# charger.net
KiCad netlist of a schematic drawn in Altium Designer
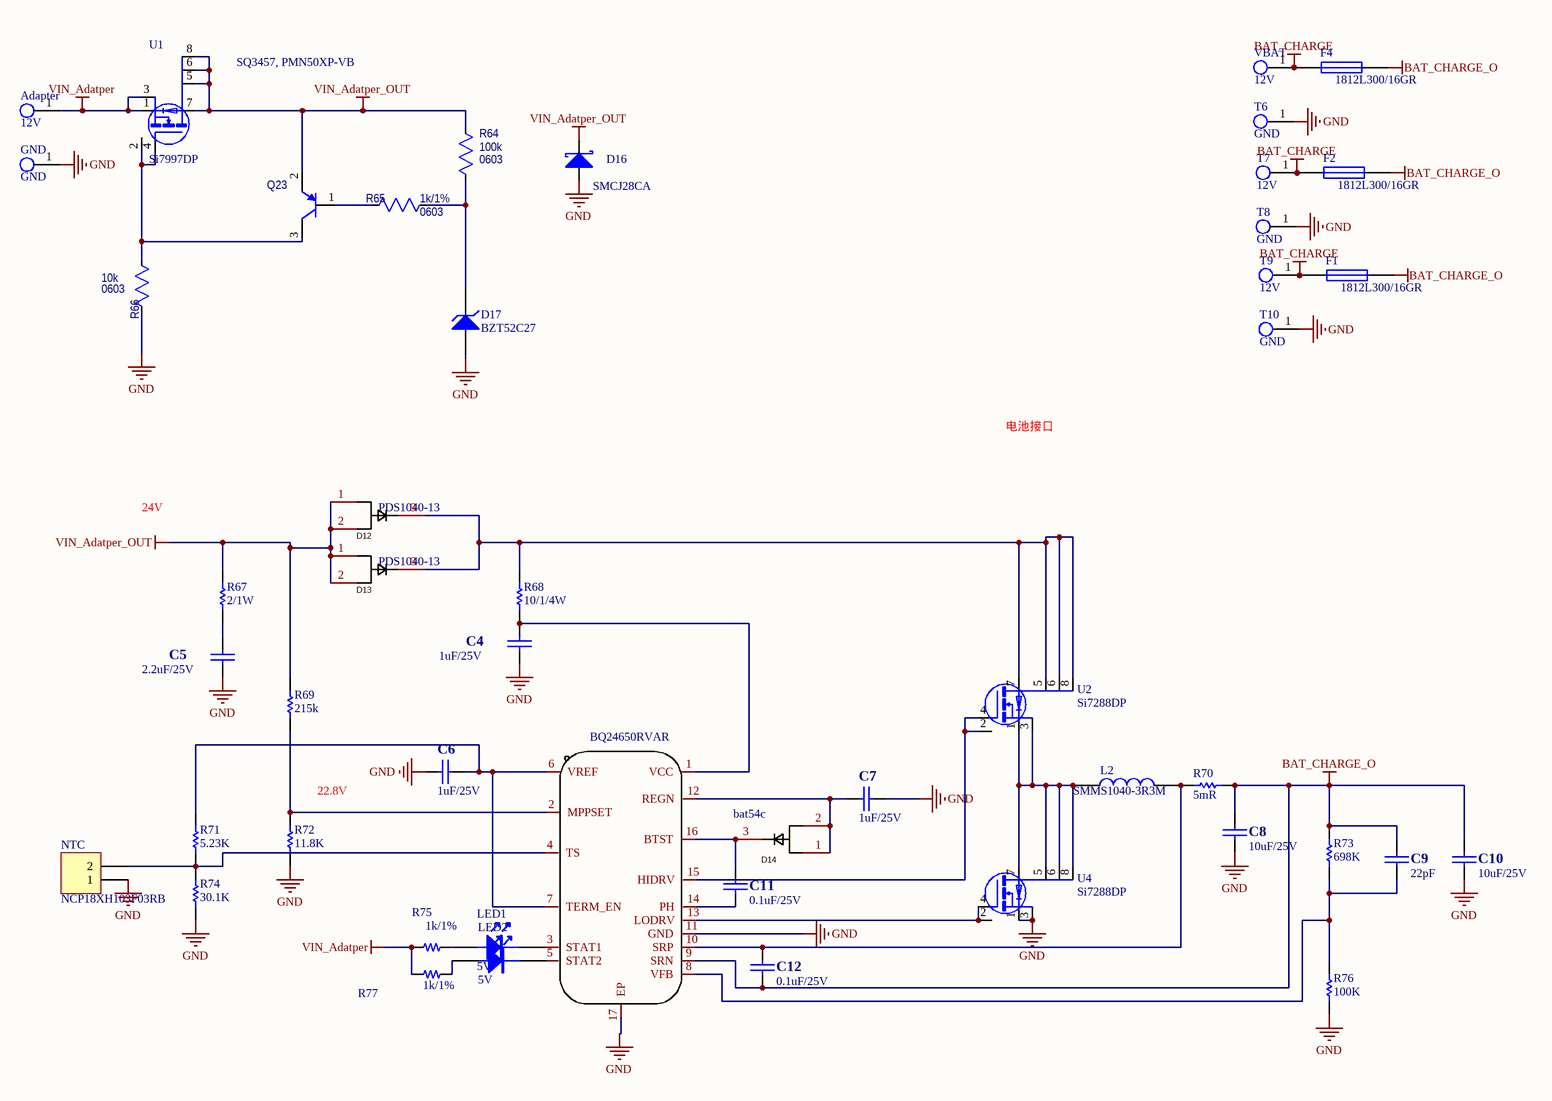
[diagram p0: charger.SchDoc]

(export (version "E")
  (design (tool "Eeschema 10.0.6"))
  (components
    (comp (ref "Adapter") (value "12V") (footprint "FIX-4.5") (libsource (lib "Schlib_20110825") (part "TP")))
    (comp (ref "C4")
      (value "1uF/25V")
      (footprint "0805C")
      (description "Capacitor")
      (libsource (lib "*") (part "CAP"))
    )
    (comp (ref "C5")
      (value "2.2uF/25V")
      (footprint "1210C")
      (description "Capacitor")
      (libsource (lib "*") (part "CAP"))
    )
    (comp (ref "C6")
      (value "1uF/25V")
      (footprint "0603C")
      (description "Capacitor")
      (libsource (lib "*") (part "CAP"))
    )
    (comp (ref "C7")
      (value "1uF/25V")
      (footprint "0603C")
      (description "Capacitor")
      (libsource (lib "*") (part "CAP"))
    )
    (comp (ref "C8")
      (value "10uF/25V")
      (footprint "0603C")
      (description "Capacitor")
      (libsource (lib "*") (part "CAP"))
    )
    (comp (ref "C9")
      (value "22pF")
      (footprint "0603C")
      (description "Capacitor")
      (libsource (lib "*") (part "CAP"))
    )
    (comp (ref "C10")
      (value "10uF/25V")
      (footprint "0603C")
      (description "Capacitor")
      (libsource (lib "*") (part "CAP"))
    )
    (comp (ref "C11")
      (value "0.1uF/25V")
      (footprint "0603C")
      (description "Capacitor")
      (libsource (lib "*") (part "CAP"))
    )
    (comp (ref "C12")
      (value "0.1uF/25V")
      (footprint "0603C")
      (description "Capacitor")
      (libsource (lib "*") (part "CAP"))
    )
    (comp (ref "D12")
      (value "PDS1040-13")
      (footprint "POWERDI-5_L5.4-W4.0-LS6.5-RD")
      (fields (field (name "MANUFACTURER") "DIODES(美台)"))
      (libsource (lib "Schlib_20110825") (part "PDS1040-13"))
    )
    (comp (ref "D13")
      (value "PDS1040-13")
      (footprint "POWERDI-5_L5.4-W4.0-LS6.5-RD")
      (fields (field (name "MANUFACTURER") "DIODES(美台)"))
      (libsource (lib "Schlib_20110825") (part "PDS1040-13"))
    )
    (comp (ref "D14")
      (value "bat54c")
      (footprint "sot23-3")
      (fields (field (name "MANUFACTURER") "DIODES(美台)") (field (name "MANUFACTURER PART") "PDS1040-13"))
      (libsource (lib "Schlib_20110825") (part "PDS1040-13"))
    )
    (comp (ref "D16")
      (value "SMCJ28CA")
      (footprint "SMC")
      (description "Schottky Diode")
      (libsource (lib "*") (part "DIODE S"))
    )
    (comp (ref "D17")
      (value "BZT52C27")
      (footprint "sod123")
      (libsource (lib "Bogen") (part "BZT52C12S-7-F"))
    )
    (comp (ref "F1")
      (value "1812L300/16GR")
      (footprint "1812-F")
      (description "Fuse")
      (fields (field (name "PUBLISHER") "Altium Limited"))
      (libsource (lib "Miscellaneous Devices") (part "Fuse 1"))
    )
    (comp (ref "F2")
      (value "1812L300/16GR")
      (footprint "1812-F")
      (description "Fuse")
      (fields (field (name "PUBLISHER") "Altium Limited"))
      (libsource (lib "Miscellaneous Devices") (part "Fuse 1"))
    )
    (comp (ref "F4")
      (value "1812L300/16GR")
      (footprint "1812-F")
      (description "Fuse")
      (fields (field (name "PUBLISHER") "Altium Limited"))
      (libsource (lib "Miscellaneous Devices") (part "Fuse 1"))
    )
    (comp (ref "GND") (value "GND") (footprint "FIX-4.5") (libsource (lib "Schlib_20110825") (part "TP")))
    (comp (ref "L2") (value "SMMS1040-3R3M") (footprint "MSS1038") (libsource (lib "*") (part "INDUCTOR")))
    (comp (ref "LED1") (value "5V") (footprint "0603LED") (libsource (lib "*") (part "LED")))
    (comp (ref "LED2") (value "5V") (footprint "0603LED") (libsource (lib "*") (part "LED")))
    (comp (ref "NTC")
      (value "NCP18XH103F03RB")
      (footprint "HDR1X2")
      (description "XH2.54 2P 立贴")
      (fields (field (name "PUBLISHER") "Altium Limited"))
      (libsource (lib "Miscellaneous Connectors") (part "Header 2"))
    )
    (comp (ref "Q23")
      (value "MMBT4403-7-F")
      (footprint "SOT23-3")
      (libsource (lib "Karl") (part "OEM_Diodes_MMBT4403"))
    )
    (comp (ref "R64")
      (value "100k")
      (footprint "RESC1608X055N_0603")
      (fields
        (field (name "PARTNUMBER") "RC0603FR-0716K9L")
        (field (name "TOLERANCE") "tol")
        (field (name "PACKAGE") "0603")
      )
      (libsource (lib "Karl") (part "Resistor_0603"))
    )
    (comp (ref "R65")
      (value "1k/1%")
      (footprint "RESC1608X055N_0603")
      (fields
        (field (name "PARTNUMBER") "RC0603FR-071KL")
        (field (name "TOLERANCE") "tol")
        (field (name "PACKAGE") "0603")
      )
      (libsource (lib "Karl") (part "Resistor_0603"))
    )
    (comp (ref "R66")
      (value "10k")
      (footprint "RESC1608X055N_0603")
      (fields
        (field (name "PARTNUMBER") "RC0603FR-071KL")
        (field (name "TOLERANCE") "tol")
        (field (name "PACKAGE") "0603")
      )
      (libsource (lib "Karl") (part "Resistor_0603"))
    )
    (comp (ref "R67")
      (value "2/1W")
      (footprint "2512R")
      (description "Resistor")
      (fields (field (name "PUBLISHER") "Altium Limited"))
      (libsource (lib "Miscellaneous Devices") (part "Res1"))
    )
    (comp (ref "R68")
      (value "10/1/4W")
      (footprint "1206R")
      (description "Resistor")
      (fields (field (name "PUBLISHER") "Altium Limited"))
      (libsource (lib "Miscellaneous Devices") (part "Res1"))
    )
    (comp (ref "R69")
      (value "215k")
      (footprint "0603R")
      (description "Resistor")
      (fields (field (name "PUBLISHER") "Altium Limited"))
      (libsource (lib "Miscellaneous Devices") (part "Res1"))
    )
    (comp (ref "R70")
      (value "5mR")
      (footprint "2512R")
      (description "Resistor")
      (fields (field (name "PUBLISHER") "Altium Limited"))
      (libsource (lib "Miscellaneous Devices") (part "Res1"))
    )
    (comp (ref "R71")
      (value "5.23K")
      (footprint "0603R")
      (description "Resistor")
      (fields (field (name "PUBLISHER") "Altium Limited"))
      (libsource (lib "Miscellaneous Devices") (part "Res1"))
    )
    (comp (ref "R72")
      (value "11.8K")
      (footprint "0603R")
      (description "Resistor")
      (fields (field (name "PUBLISHER") "Altium Limited"))
      (libsource (lib "Miscellaneous Devices") (part "Res1"))
    )
    (comp (ref "R73")
      (value "698K")
      (footprint "0603R")
      (description "Resistor")
      (fields (field (name "PUBLISHER") "Altium Limited"))
      (libsource (lib "Miscellaneous Devices") (part "Res1"))
    )
    (comp (ref "R74")
      (value "30.1K")
      (footprint "0603R")
      (description "Resistor")
      (fields (field (name "PUBLISHER") "Altium Limited"))
      (libsource (lib "Miscellaneous Devices") (part "Res1"))
    )
    (comp (ref "R75") (value "1k/1%") (footprint "0603R") (libsource (lib "JRJ_1") (part "R")))
    (comp (ref "R76")
      (value "100K")
      (footprint "0603R")
      (description "Resistor")
      (fields (field (name "PUBLISHER") "Altium Limited"))
      (libsource (lib "Miscellaneous Devices") (part "Res1"))
    )
    (comp (ref "R77") (value "1k/1%") (footprint "0603R") (libsource (lib "JRJ_1") (part "R")))
    (comp (ref "T6") (value "GND") (footprint "FIX-4.5") (libsource (lib "Schlib_20110825") (part "TP")))
    (comp (ref "T7") (value "12V") (footprint "FIX-4.5") (libsource (lib "Schlib_20110825") (part "TP")))
    (comp (ref "T8") (value "GND") (footprint "FIX-4.5") (libsource (lib "Schlib_20110825") (part "TP")))
    (comp (ref "T9") (value "12V") (footprint "FIX-4.5") (libsource (lib "Schlib_20110825") (part "TP")))
    (comp (ref "T10") (value "GND") (footprint "FIX-4.5") (libsource (lib "Schlib_20110825") (part "TP")))
    (comp (ref "U1")
      (value "Si7997DP")
      (footprint "PowerPAK SO-8")
      (description "Sia430DJ")
      (libsource (lib "Schlib_20110825") (part "Si7997DP"))
    )
    (comp (ref "U2")
      (value "Si7288DP")
      (footprint "PowerPAK SO-8")
      (description "Sia430DJ")
      (libsource (lib "Schlib_20110825") (part "Si7997DP"))
    )
    (comp (ref "U4")
      (value "Si7288DP")
      (footprint "PowerPAK SO-8")
      (description "Sia430DJ")
      (libsource (lib "Schlib_20110825") (part "Si7997DP"))
    )
    (comp (ref "U5")
      (value "BQ24650RVAR")
      (footprint "VQFN-16_L3.6-W3.6-P0.50-BL-EP")
      (fields (field (name "MANUFACTURER") "TI(德州仪器)"))
      (libsource (lib "Schlib_20110825") (part "BQ24650RVAR"))
    )
    (comp (ref "VBAT") (value "12V") (footprint "FIX-4.5") (libsource (lib "Schlib_20110825") (part "TP")))
  )
  (nets
    (net (code "1") (name "BAT_CHARGE") (class "Default")
      (node (ref "F1") (pin "1") (pinfunction "1_1") (pintype "passive"))
      (node (ref "F2") (pin "1") (pinfunction "1_1") (pintype "passive"))
      (node (ref "F4") (pin "1") (pinfunction "1_1") (pintype "passive"))
      (node (ref "T7") (pin "1") (pintype "passive"))
      (node (ref "T9") (pin "1") (pintype "passive"))
      (node (ref "VBAT") (pin "1") (pintype "passive"))
    )
    (net (code "2") (name "BAT_CHARGE_O") (class "Default")
      (node (ref "C10") (pin "2") (pinfunction "2_2") (pintype "passive"))
      (node (ref "C12") (pin "1") (pinfunction "1_1") (pintype "passive"))
      (node (ref "C8") (pin "2") (pinfunction "2_2") (pintype "passive"))
      (node (ref "C9") (pin "2") (pinfunction "2_2") (pintype "passive"))
      (node (ref "F1") (pin "2") (pinfunction "2_2") (pintype "passive"))
      (node (ref "F2") (pin "2") (pinfunction "2_2") (pintype "passive"))
      (node (ref "F4") (pin "2") (pinfunction "2_2") (pintype "passive"))
      (node (ref "R70") (pin "2") (pinfunction "2_2") (pintype "passive"))
      (node (ref "R73") (pin "1") (pinfunction "1_1") (pintype "passive"))
      (node (ref "U5") (pin "9") (pinfunction "SRN_9") (pintype "passive"))
    )
    (net (code "3") (name "GND") (class "Default")
      (node (ref "C10") (pin "1") (pinfunction "1_1") (pintype "passive"))
      (node (ref "C4") (pin "2") (pinfunction "2_2") (pintype "passive"))
      (node (ref "C5") (pin "2") (pinfunction "2_2") (pintype "passive"))
      (node (ref "C6") (pin "1") (pinfunction "1_1") (pintype "passive"))
      (node (ref "C7") (pin "2") (pinfunction "2_2") (pintype "passive"))
      (node (ref "C8") (pin "1") (pinfunction "1_1") (pintype "passive"))
      (node (ref "D16") (pin "1") (pinfunction "A_1") (pintype "passive"))
      (node (ref "D17") (pin "1") (pinfunction "A_1") (pintype "passive"))
      (node (ref "GND") (pin "1") (pintype "passive"))
      (node (ref "NTC") (pin "1") (pinfunction "1_1") (pintype "passive"))
      (node (ref "R66") (pin "2") (pinfunction "2_2") (pintype "passive"))
      (node (ref "R72") (pin "2") (pinfunction "2_2") (pintype "passive"))
      (node (ref "R74") (pin "2") (pinfunction "2_2") (pintype "passive"))
      (node (ref "R76") (pin "2") (pinfunction "2_2") (pintype "passive"))
      (node (ref "T10") (pin "1") (pintype "passive"))
      (node (ref "T6") (pin "1") (pintype "passive"))
      (node (ref "T8") (pin "1") (pintype "passive"))
      (node (ref "U4") (pin "1") (pinfunction "S_1") (pintype "passive"))
      (node (ref "U4") (pin "3") (pinfunction "S_3") (pintype "passive"))
      (node (ref "U5") (pin "11") (pinfunction "GND_11") (pintype "passive"))
      (node (ref "U5") (pin "17") (pinfunction "EP_17") (pintype "passive"))
    )
    (net (code "4") (name "Net-(C5-Pad1)") (class "Default")
      (node (ref "C5") (pin "1") (pinfunction "1_1") (pintype "passive"))
      (node (ref "R67") (pin "2") (pinfunction "2_2") (pintype "passive"))
    )
    (net (code "5") (name "Net-(D12-Pad3)") (class "Default")
      (node (ref "D12") (pin "3") (pinfunction "3_3") (pintype "passive"))
      (node (ref "D13") (pin "3") (pinfunction "3_3") (pintype "passive"))
      (node (ref "R68") (pin "1") (pinfunction "1_1") (pintype "passive"))
      (node (ref "U2") (pin "5") (pinfunction "D_5") (pintype "passive"))
      (node (ref "U2") (pin "6") (pinfunction "D_6") (pintype "passive"))
      (node (ref "U2") (pin "7") (pinfunction "D_7") (pintype "passive"))
      (node (ref "U2") (pin "8") (pinfunction "D_8") (pintype "passive"))
    )
    (net (code "6") (name "Net-(D14-LEFT)") (class "Default")
      (node (ref "C7") (pin "1") (pinfunction "1_1") (pintype "passive"))
      (node (ref "D14") (pin "1") (pinfunction "LEFT_1") (pintype "passive"))
      (node (ref "D14") (pin "2") (pinfunction "RIGHT_2") (pintype "passive"))
      (node (ref "U5") (pin "12") (pinfunction "REGN_12") (pintype "passive"))
    )
    (net (code "7") (name "Net-(D17-K)") (class "Default")
      (node (ref "D17") (pin "2") (pinfunction "K_2") (pintype "passive"))
      (node (ref "R64") (pin "1") (pinfunction "1_1") (pintype "passive"))
      (node (ref "R65") (pin "1") (pinfunction "1_1") (pintype "passive"))
    )
    (net (code "8") (name "Net-(L2-Pad1)") (class "Default")
      (node (ref "L2") (pin "1") (pinfunction "1_1") (pintype "passive"))
      (node (ref "U2") (pin "1") (pinfunction "S_1") (pintype "passive"))
      (node (ref "U2") (pin "3") (pinfunction "S_3") (pintype "passive"))
      (node (ref "U4") (pin "5") (pinfunction "D_5") (pintype "passive"))
      (node (ref "U4") (pin "6") (pinfunction "D_6") (pintype "passive"))
      (node (ref "U4") (pin "7") (pinfunction "D_7") (pintype "passive"))
      (node (ref "U4") (pin "8") (pinfunction "D_8") (pintype "passive"))
    )
    (net (code "9") (name "Net-(LED1-Pad1)") (class "Default")
      (node (ref "LED1") (pin "1") (pinfunction "1_1") (pintype "passive"))
      (node (ref "R75") (pin "1") (pintype "passive"))
    )
    (net (code "10") (name "Net-(LED2-Pad1)") (class "Default")
      (node (ref "LED2") (pin "1") (pinfunction "1_1") (pintype "passive"))
      (node (ref "R77") (pin "1") (pintype "passive"))
    )
    (net (code "11") (name "Net-(Q23-B)") (class "Default")
      (node (ref "Q23") (pin "1") (pinfunction "B_1") (pintype "passive"))
      (node (ref "R65") (pin "2") (pinfunction "2_2") (pintype "passive"))
    )
    (net (code "12") (name "Net-(Q23-C)") (class "Default")
      (node (ref "Q23") (pin "3") (pinfunction "C_3") (pintype "passive"))
      (node (ref "R66") (pin "1") (pinfunction "1_1") (pintype "passive"))
      (node (ref "U1") (pin "2") (pinfunction "G_2") (pintype "passive"))
      (node (ref "U1") (pin "4") (pinfunction "G_4") (pintype "passive"))
    )
    (net (code "13") (name "Net-(U5-BTST)") (class "Default")
      (node (ref "C11") (pin "2") (pinfunction "2_2") (pintype "passive"))
      (node (ref "D14") (pin "3") (pinfunction "3_3") (pintype "passive"))
      (node (ref "U5") (pin "16") (pinfunction "BTST_16") (pintype "passive"))
    )
    (net (code "14") (name "Net-(U5-HIDRV)") (class "Default")
      (node (ref "U2") (pin "2") (pinfunction "G_2") (pintype "passive"))
      (node (ref "U2") (pin "4") (pinfunction "G_4") (pintype "passive"))
      (node (ref "U5") (pin "15") (pinfunction "HIDRV_15") (pintype "passive"))
    )
    (net (code "15") (name "Net-(U5-LODRV)") (class "Default")
      (node (ref "U4") (pin "2") (pinfunction "G_2") (pintype "passive"))
      (node (ref "U4") (pin "4") (pinfunction "G_4") (pintype "passive"))
      (node (ref "U5") (pin "13") (pinfunction "LODRV_13") (pintype "passive"))
    )
    (net (code "16") (name "Net-(U5-MPPSET)") (class "Default")
      (node (ref "R69") (pin "2") (pinfunction "2_2") (pintype "passive"))
      (node (ref "R72") (pin "1") (pinfunction "1_1") (pintype "passive"))
      (node (ref "U5") (pin "2") (pinfunction "MPPSET_2") (pintype "passive"))
    )
    (net (code "17") (name "Net-(U5-PH)") (class "Default")
      (node (ref "C11") (pin "1") (pinfunction "1_1") (pintype "passive"))
      (node (ref "U5") (pin "14") (pinfunction "PH_14") (pintype "passive"))
    )
    (net (code "18") (name "Net-(U5-SRP)") (class "Default")
      (node (ref "C12") (pin "2") (pinfunction "2_2") (pintype "passive"))
      (node (ref "L2") (pin "2") (pinfunction "2_2") (pintype "passive"))
      (node (ref "R70") (pin "1") (pinfunction "1_1") (pintype "passive"))
      (node (ref "U5") (pin "10") (pinfunction "SRP_10") (pintype "passive"))
    )
    (net (code "19") (name "Net-(U5-STAT1)") (class "Default")
      (node (ref "LED1") (pin "2") (pinfunction "2_2") (pintype "passive"))
      (node (ref "U5") (pin "3") (pinfunction "STAT1_3") (pintype "passive"))
    )
    (net (code "20") (name "Net-(U5-TERM_EN)") (class "Default")
      (node (ref "C6") (pin "2") (pinfunction "2_2") (pintype "passive"))
      (node (ref "R71") (pin "1") (pinfunction "1_1") (pintype "passive"))
      (node (ref "U5") (pin "6") (pinfunction "VREF_6") (pintype "passive"))
      (node (ref "U5") (pin "7") (pinfunction "TERM_EN_7") (pintype "passive"))
    )
    (net (code "21") (name "Net-(U5-TS)") (class "Default")
      (node (ref "NTC") (pin "2") (pinfunction "2_2") (pintype "passive"))
      (node (ref "R71") (pin "2") (pinfunction "2_2") (pintype "passive"))
      (node (ref "R74") (pin "1") (pinfunction "1_1") (pintype "passive"))
      (node (ref "U5") (pin "4") (pinfunction "TS_4") (pintype "passive"))
    )
    (net (code "22") (name "Net-(U5-VCC)") (class "Default")
      (node (ref "C4") (pin "1") (pinfunction "1_1") (pintype "passive"))
      (node (ref "R68") (pin "2") (pinfunction "2_2") (pintype "passive"))
      (node (ref "U5") (pin "1") (pinfunction "VCC_1") (pintype "passive"))
    )
    (net (code "23") (name "Net-(U5-VFB)") (class "Default")
      (node (ref "C9") (pin "1") (pinfunction "1_1") (pintype "passive"))
      (node (ref "R73") (pin "2") (pinfunction "2_2") (pintype "passive"))
      (node (ref "R76") (pin "1") (pinfunction "1_1") (pintype "passive"))
      (node (ref "U5") (pin "8") (pinfunction "VFB_8") (pintype "passive"))
    )
    (net (code "24") (name "VIN_Adatper") (class "Default")
      (node (ref "Adapter") (pin "1") (pintype "passive"))
      (node (ref "R75") (pin "2") (pintype "passive"))
      (node (ref "R77") (pin "2") (pintype "passive"))
      (node (ref "U1") (pin "1") (pinfunction "S_1") (pintype "passive"))
      (node (ref "U1") (pin "3") (pinfunction "S_3") (pintype "passive"))
    )
    (net (code "25") (name "VIN_Adatper_OUT") (class "Default")
      (node (ref "D12") (pin "1") (pinfunction "LEFT_1") (pintype "passive"))
      (node (ref "D12") (pin "2") (pinfunction "RIGHT_2") (pintype "passive"))
      (node (ref "D13") (pin "1") (pinfunction "LEFT_1") (pintype "passive"))
      (node (ref "D13") (pin "2") (pinfunction "RIGHT_2") (pintype "passive"))
      (node (ref "D16") (pin "2") (pinfunction "K_2") (pintype "passive"))
      (node (ref "Q23") (pin "2") (pinfunction "E_2") (pintype "passive"))
      (node (ref "R64") (pin "2") (pinfunction "2_2") (pintype "passive"))
      (node (ref "R67") (pin "1") (pinfunction "1_1") (pintype "passive"))
      (node (ref "R69") (pin "1") (pinfunction "1_1") (pintype "passive"))
      (node (ref "U1") (pin "5") (pinfunction "D_5") (pintype "passive"))
      (node (ref "U1") (pin "6") (pinfunction "D_6") (pintype "passive"))
      (node (ref "U1") (pin "7") (pinfunction "D_7") (pintype "passive"))
      (node (ref "U1") (pin "8") (pinfunction "D_8") (pintype "passive"))
    )
    (net (code "26") (name "unconnected-(LED2-Pad2)") (class "Default")
      (node (ref "LED2") (pin "2") (pinfunction "2_2") (pintype "passive"))
    )
    (net (code "27") (name "unconnected-(U5-STAT2-Pad5)") (class "Default")
      (node (ref "U5") (pin "5") (pinfunction "STAT2_5") (pintype "passive"))
    )
  )
)
